# SPIdisplay-8x7seg.net
KiCad netlist of a schematic drawn in EAGLE
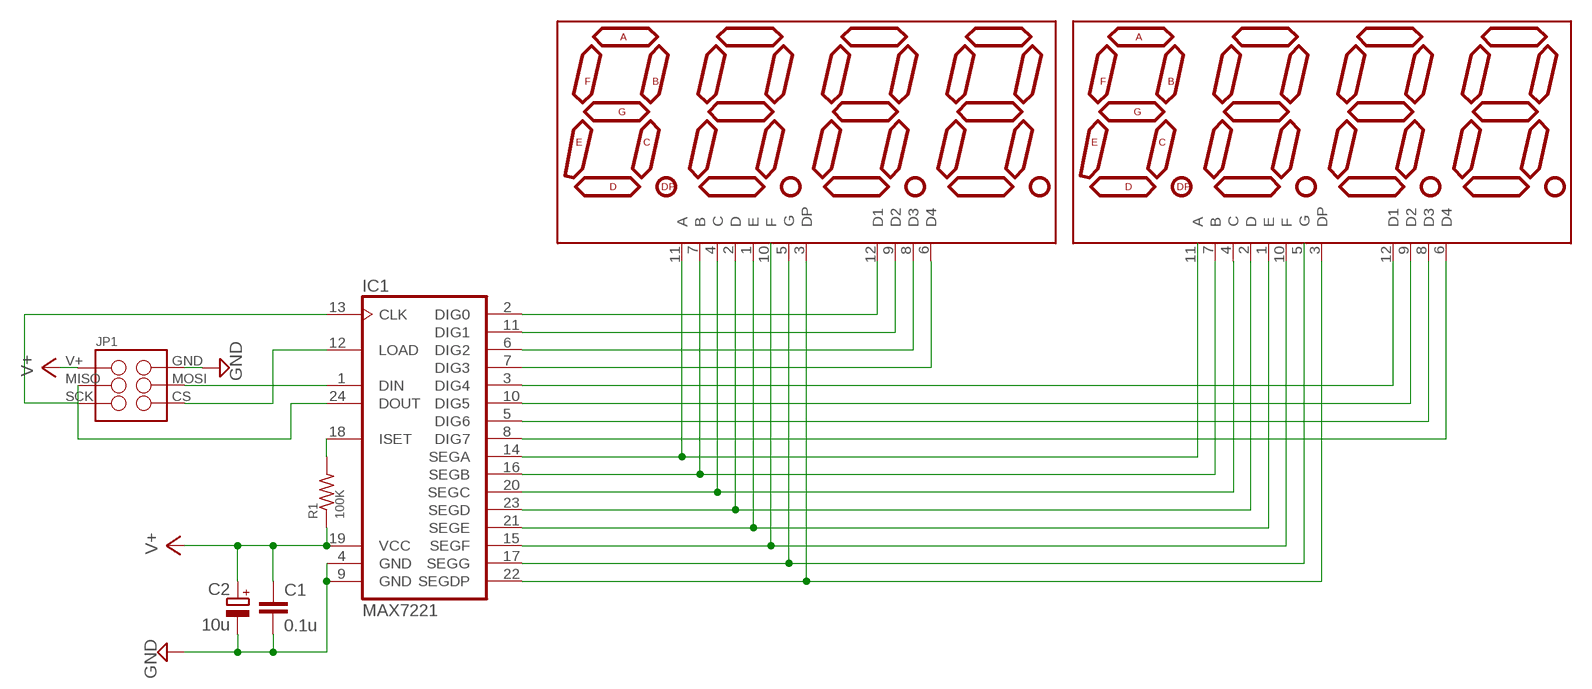
[diagram p0: schematic, sheet 1]

(export (version "E")
  (design (tool "Eeschema 10.0.6"))
  (components
    (comp (ref "C1")
      (value "0.1u")
      (footprint "eagle-import:C050-025X075")
      (libsource (lib "eagle-import") (part "C-EU050-025X075"))
    )
    (comp (ref "C2")
      (value "10u")
      (footprint "eagle-import:E2,5-5")
      (libsource (lib "eagle-import") (part "CPOL-EUE2.5-5"))
    )
    (comp (ref "DISP1")
      (value "7-SEG-4DIG-LD-3461AS-HP-BUBBLE")
      (footprint "eagle-import:DIL12")
      (libsource (lib "eagle-import") (part "7-SEG-4DIG-LD-3461AS-HP-BUBBLE"))
    )
    (comp (ref "DISP2")
      (value "7-SEG-4DIG-LD-3461AS-HP-BUBBLE")
      (footprint "eagle-import:DIL12")
      (libsource (lib "eagle-import") (part "7-SEG-4DIG-LD-3461AS-HP-BUBBLE"))
    )
    (comp (ref "IC1")
      (value "MAX7221")
      (footprint "eagle-import:DIL24-3")
      (fields (field (name "MF") "MAXIM"))
      (libsource (lib "eagle-import") (part "MAX7221"))
    )
    (comp (ref "JP1")
      (value "M03X2SHROUD")
      (footprint "eagle-import:2X3-SPI-SHROUDED")
      (libsource (lib "eagle-import") (part "M03X2SHROUD"))
    )
    (comp (ref "R1")
      (value "100K")
      (footprint "eagle-import:0207_10")
      (libsource (lib "eagle-import") (part "R-US_0207/10"))
    )
  )
  (nets
    (net (code "1") (name "GND") (class "Default")
      (node (ref "C1") (pin "2") (pinfunction "2_2") (pintype "passive"))
      (node (ref "C2") (pin "-") (pinfunction "-_-") (pintype "passive"))
      (node (ref "IC1") (pin "4") (pinfunction "GND_4") (pintype "power_in"))
      (node (ref "IC1") (pin "9") (pinfunction "GND_9") (pintype "power_in"))
      (node (ref "JP1") (pin "2") (pinfunction "2_2") (pintype "bidirectional"))
    )
    (net (code "2") (name "Net-(DISP1-A)") (class "Default")
      (node (ref "DISP1") (pin "11") (pinfunction "A_11") (pintype "bidirectional"))
      (node (ref "IC1") (pin "14") (pinfunction "SEGA_14") (pintype "output"))
    )
    (net (code "3") (name "Net-(DISP1-B)") (class "Default")
      (node (ref "DISP1") (pin "7") (pinfunction "B_7") (pintype "bidirectional"))
      (node (ref "DISP2") (pin "7") (pinfunction "B_7") (pintype "bidirectional"))
      (node (ref "IC1") (pin "16") (pinfunction "SEGB_16") (pintype "output"))
    )
    (net (code "4") (name "Net-(DISP1-C)") (class "Default")
      (node (ref "DISP1") (pin "4") (pinfunction "C_4") (pintype "bidirectional"))
      (node (ref "DISP2") (pin "4") (pinfunction "C_4") (pintype "bidirectional"))
      (node (ref "IC1") (pin "20") (pinfunction "SEGC_20") (pintype "output"))
    )
    (net (code "5") (name "Net-(DISP1-D)") (class "Default")
      (node (ref "DISP1") (pin "2") (pinfunction "D_2") (pintype "bidirectional"))
      (node (ref "DISP2") (pin "2") (pinfunction "D_2") (pintype "bidirectional"))
      (node (ref "IC1") (pin "23") (pinfunction "SEGD_23") (pintype "output"))
    )
    (net (code "6") (name "Net-(DISP1-D1)") (class "Default")
      (node (ref "DISP1") (pin "12") (pinfunction "D1_12") (pintype "bidirectional"))
      (node (ref "IC1") (pin "2") (pinfunction "DIG0_2") (pintype "output"))
    )
    (net (code "7") (name "Net-(DISP1-D2)") (class "Default")
      (node (ref "DISP1") (pin "9") (pinfunction "D2_9") (pintype "bidirectional"))
      (node (ref "IC1") (pin "11") (pinfunction "DIG1_11") (pintype "output"))
    )
    (net (code "8") (name "Net-(DISP1-D3)") (class "Default")
      (node (ref "DISP1") (pin "8") (pinfunction "D3_8") (pintype "bidirectional"))
      (node (ref "IC1") (pin "6") (pinfunction "DIG2_6") (pintype "output"))
    )
    (net (code "9") (name "Net-(DISP1-D4)") (class "Default")
      (node (ref "DISP1") (pin "6") (pinfunction "D4_6") (pintype "bidirectional"))
      (node (ref "IC1") (pin "7") (pinfunction "DIG3_7") (pintype "output"))
    )
    (net (code "10") (name "Net-(DISP1-DP)") (class "Default")
      (node (ref "DISP1") (pin "3") (pinfunction "DP_3") (pintype "bidirectional"))
      (node (ref "DISP2") (pin "3") (pinfunction "DP_3") (pintype "bidirectional"))
      (node (ref "IC1") (pin "22") (pinfunction "SEGDP_22") (pintype "output"))
    )
    (net (code "11") (name "Net-(DISP1-E)") (class "Default")
      (node (ref "DISP1") (pin "1") (pinfunction "E_1") (pintype "bidirectional"))
      (node (ref "DISP2") (pin "1") (pinfunction "E_1") (pintype "bidirectional"))
      (node (ref "IC1") (pin "21") (pinfunction "SEGE_21") (pintype "output"))
    )
    (net (code "12") (name "Net-(DISP1-G)") (class "Default")
      (node (ref "DISP1") (pin "5") (pinfunction "G_5") (pintype "bidirectional"))
      (node (ref "IC1") (pin "17") (pinfunction "SEGG_17") (pintype "output"))
    )
    (net (code "13") (name "Net-(DISP2-D1)") (class "Default")
      (node (ref "DISP2") (pin "12") (pinfunction "D1_12") (pintype "bidirectional"))
      (node (ref "IC1") (pin "3") (pinfunction "DIG4_3") (pintype "output"))
    )
    (net (code "14") (name "Net-(DISP2-D2)") (class "Default")
      (node (ref "DISP2") (pin "9") (pinfunction "D2_9") (pintype "bidirectional"))
      (node (ref "IC1") (pin "10") (pinfunction "DIG5_10") (pintype "output"))
    )
    (net (code "15") (name "Net-(DISP2-D3)") (class "Default")
      (node (ref "DISP2") (pin "8") (pinfunction "D3_8") (pintype "bidirectional"))
      (node (ref "IC1") (pin "5") (pinfunction "DIG6_5") (pintype "output"))
    )
    (net (code "16") (name "Net-(DISP2-D4)") (class "Default")
      (node (ref "DISP2") (pin "6") (pinfunction "D4_6") (pintype "bidirectional"))
      (node (ref "IC1") (pin "8") (pinfunction "DIG7_8") (pintype "output"))
    )
    (net (code "17") (name "Net-(DISP2-F)") (class "Default")
      (node (ref "DISP2") (pin "10") (pinfunction "F_10") (pintype "bidirectional"))
      (node (ref "IC1") (pin "15") (pinfunction "SEGF_15") (pintype "output"))
    )
    (net (code "18") (name "Net-(IC1-CLK)") (class "Default")
      (node (ref "IC1") (pin "13") (pinfunction "CLK_13") (pintype "input"))
      (node (ref "JP1") (pin "5") (pinfunction "5_5") (pintype "bidirectional"))
    )
    (net (code "19") (name "Net-(IC1-DIN)") (class "Default")
      (node (ref "IC1") (pin "1") (pinfunction "DIN_1") (pintype "input"))
      (node (ref "JP1") (pin "4") (pinfunction "4_4") (pintype "bidirectional"))
    )
    (net (code "20") (name "Net-(IC1-DOUT)") (class "Default")
      (node (ref "IC1") (pin "24") (pinfunction "DOUT_24") (pintype "output"))
      (node (ref "JP1") (pin "3") (pinfunction "3_3") (pintype "bidirectional"))
    )
    (net (code "21") (name "Net-(IC1-ISET)") (class "Default")
      (node (ref "IC1") (pin "18") (pinfunction "ISET_18") (pintype "input"))
      (node (ref "R1") (pin "2") (pinfunction "2_2") (pintype "passive"))
    )
    (net (code "22") (name "Net-(IC1-LOAD)") (class "Default")
      (node (ref "IC1") (pin "12") (pinfunction "LOAD_12") (pintype "input"))
      (node (ref "JP1") (pin "6") (pinfunction "6_6") (pintype "bidirectional"))
    )
    (net (code "23") (name "V+") (class "Default")
      (node (ref "C1") (pin "1") (pinfunction "1_1") (pintype "passive"))
      (node (ref "C2") (pin "+") (pinfunction "+_+") (pintype "passive"))
      (node (ref "IC1") (pin "19") (pinfunction "VCC_19") (pintype "power_in"))
      (node (ref "JP1") (pin "1") (pinfunction "1_1") (pintype "bidirectional"))
      (node (ref "R1") (pin "1") (pinfunction "1_1") (pintype "passive"))
    )
    (net (code "24") (name "unconnected-(DISP1-F-Pad10)") (class "Default")
      (node (ref "DISP1") (pin "10") (pinfunction "F_10") (pintype "bidirectional"))
    )
    (net (code "25") (name "unconnected-(DISP2-A-Pad11)") (class "Default")
      (node (ref "DISP2") (pin "11") (pinfunction "A_11") (pintype "bidirectional"))
    )
    (net (code "26") (name "unconnected-(DISP2-G-Pad5)") (class "Default")
      (node (ref "DISP2") (pin "5") (pinfunction "G_5") (pintype "bidirectional"))
    )
  )
)
